# MotherboardSupply.net
KiCad netlist of a schematic drawn in Altium Designer
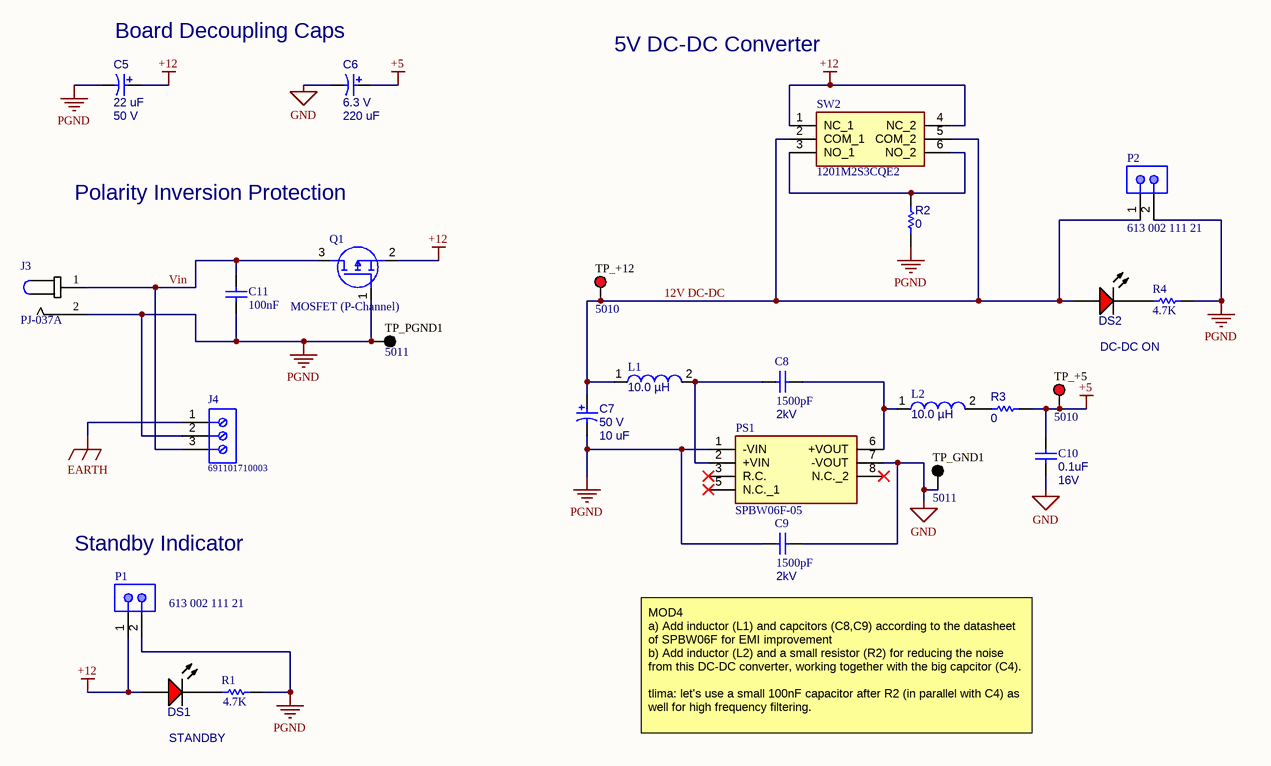
[diagram p0: MotherboardSupply.SchDoc]

(export (version "E")
  (design (tool "Eeschema 10.0.6"))
  (components
    (comp (ref "C5")
      (value "UUD1H220MCL1GS")
      (footprint "NIC-CAPA2-6.3X5.8_V")
      (fields
        (field (name "MANUFACTURER") "Nichicon")
        (field (name "RATED CAPACITANCE") "22 uF")
        (field (name "RATED VOLTAGE") "50 V")
      )
      (libsource (lib "Altium Content Vault") (part "NIC-CAP-P-2"))
    )
    (comp (ref "C6")
      (value "UUD0J221MCL1GS")
      (footprint "NIC-CAPA2-6.3X5.8_V")
      (fields
        (field (name "RATED VOLTAGE") "6.3 V")
        (field (name "RATED CAPACITANCE") "220 uF")
        (field (name "MANUFACTURER") "Nichicon")
      )
      (libsource (lib "Altium Content Vault") (part "NIC-CAP-P-2"))
    )
    (comp (ref "C7")
      (value "UUD0J221MCL1GS")
      (footprint "NIC-CAPA2-6.3X5.8_V")
      (fields
        (field (name "RATED VOLTAGE") "50 V")
        (field (name "RATED CAPACITANCE") "10 uF")
        (field (name "MANUFACTURER") "Nichicon")
      )
      (libsource (lib "Altium Content Vault") (part "NIC-CAP-P-2"))
    )
    (comp (ref "C8")
      (value "1500pF")
      (footprint "C1206")
      (description "Capacitor (Semiconductor SIM Model)")
      (fields
        (field (name "RATED VOLTAGE") "2kV")
        (field (name "Comment") "CC1206KKX7RDBB152")
        (field (name "PUBLISHER") "Altium Limited")
      )
      (libsource (lib "Miscellaneous Devices") (part "Cap Semi"))
    )
    (comp (ref "C9")
      (value "1500pF")
      (footprint "C1206")
      (description "Capacitor (Semiconductor SIM Model)")
      (fields
        (field (name "RATED VOLTAGE") "2kV")
        (field (name "Comment") "CC1206KKX7RDBB152")
        (field (name "PUBLISHER") "Altium Limited")
      )
      (libsource (lib "Miscellaneous Devices") (part "Cap Semi"))
    )
    (comp (ref "C10")
      (value "0.1uF")
      (footprint "CAPC1608X87X35LL15T15")
      (fields
        (field (name "MANUFACTURER") "Kemet")
        (field (name "PART NUMBER") "C0603C104K4RACTU")
        (field (name "RATED VOLTAGE") "16V")
      )
      (libsource (lib "Altium Content Vault") (part "CAP"))
    )
    (comp (ref "C11")
      (value "100nF")
      (footprint "CAPC1206(3216)150_M")
      (description "CAP 100nF 250V ±10% 1206 (3216 Metric) Thickness 1.45mm SMD")
      (fields (field (name "TOLERANCE") "Â±10%"))
      (libsource (lib "Altium Content Vault") (part "CAP"))
    )
    (comp (ref "DS1")
      (value "TLMS1000-GS08")
      (footprint "VISH-TLMS1000_V")
      (description "Low Current LED, 40 mW, 1.8 V, -40 to 100 degC, 2-Pin SMD (0603), RoHS, Tape and Reel")
      (fields (field (name "MANUFACTURER") "Vishay"))
      (libsource (lib "Altium Content Vault") (part "LED-RED-AK-2"))
    )
    (comp (ref "DS2")
      (value "TLMS1000-GS08")
      (footprint "VISH-TLMS1000_V")
      (description "Low Current LED, 40 mW, 1.8 V, -40 to 100 degC, 2-Pin SMD (0603), RoHS, Tape and Reel")
      (fields (field (name "MANUFACTURER") "Vishay"))
      (libsource (lib "Altium Content Vault") (part "LED-RED-AK-2"))
    )
    (comp (ref "J3")
      (value "PJ-037A")
      (footprint "*CUI_PJ-037A")
      (description "2.0 x 6.5 mm, 2.5 A, Horizontal, Through Hole, Dc Power Jack Connector")
      (fields (field (name "DIGI-KEY_PART_NUMBER") "CP-037A-ND") (field (name "MF") "CUI Inc."))
      (libsource (lib "PJ-037A") (part "PJ-037A"))
    )
    (comp (ref "J4")
      (value "691101710003")
      (footprint "691101710003")
      (description "Series 101 - 5.00 mm Horizontal Entry Modular with Pressure Clamp WR-TBL, 3 pin")
      (fields (field (name "MANUFACTURER") "Wurth Elektronik") (field (name "PUBLISHER") "WurthElektronik"))
      (libsource (lib "Altium Content Vault") (part "WE-CN-1P-F-TB3"))
    )
    (comp (ref "L1")
      (value "74477110")
      (footprint "WE-PD-L")
      (description "SMD-Shielded Power Inductor WE-PD, L = 10.0 µH")
      (fields (field (name "INDUCTANCE") "10.0 µH"))
      (libsource (lib "Altium Content Vault") (part "PAS-IND-INDUCTOR-2"))
    )
    (comp (ref "L2")
      (value "74477110")
      (footprint "WE-PD-L")
      (description "SMD-Shielded Power Inductor WE-PD, L = 10.0 µH")
      (fields (field (name "INDUCTANCE") "10.0 µH"))
      (libsource (lib "Altium Content Vault") (part "PAS-IND-INDUCTOR-2"))
    )
    (comp (ref "P1")
      (value "613 002 111 21")
      (footprint "WE-61300211121_V")
      (libsource (lib "Altium Content Vault") (part "CN-1P-M-R2"))
    )
    (comp (ref "P2")
      (value "613 002 111 21")
      (footprint "WE-61300211121_V")
      (libsource (lib "Altium Content Vault") (part "CN-1P-M-R2"))
    )
    (comp (ref "PS1")
      (value "SPBW06F-05")
      (footprint "SamacSys:SPBW06F05")
      (description "Power Supply")
      (fields (field (name "MOUSER PART NUMBER") "709-SPBW06F-05"))
      (libsource (lib "*") (part "SPBW06F-05"))
    )
    (comp (ref "Q1")
      (value "MOSFET (P-Channel)")
      (footprint "SamacSys:FFSB20120AF085")
      (description "FQB47P06TM-AM002")
      (fields (field (name "MOUSER PART NUMBER") "512-FQB47P06TM_AM002"))
      (libsource (lib "*") (part "FQB47P06TM-AM002"))
    )
    (comp (ref "R1")
      (value "4.7K")
      (footprint "RESC3216X60X45ML10T20")
      (description "CRCW12064K70JNEB")
      (fields (field (name "MANUFACTURER") "Vishay Dale"))
      (libsource (lib "Altium Content Vault") (part "RES"))
    )
    (comp (ref "R2")
      (value "0")
      (footprint "RESC3216X105X45ML10T20")
      (description "CRCW12060000Z0EA")
      (fields (field (name "MANUFACTURER") "Vishay Dale"))
      (libsource (lib "Altium Content Vault") (part "RES"))
    )
    (comp (ref "R3")
      (value "0")
      (footprint "RESC3216X105X45ML10T20")
      (description "CRCW12060000Z0EA")
      (fields (field (name "MANUFACTURER") "Vishay Dale"))
      (libsource (lib "Altium Content Vault") (part "RES"))
    )
    (comp (ref "R4")
      (value "4.7K")
      (footprint "RESC3216X60X45ML10T20")
      (description "CRCW12064K70JNEB")
      (fields (field (name "MANUFACTURER") "Vishay Dale"))
      (libsource (lib "Altium Content Vault") (part "RES"))
    )
    (comp (ref "SW2")
      (value "1201M2S3CQE2")
      (footprint "SamacSys:1201M2S3CQE2")
      (description "Switch")
      (fields (field (name "MOUSER PART NUMBER") "611-1201M2S3CQE2"))
      (libsource (lib "*") (part "1201M2S3CQE2"))
    )
    (comp (ref "TP_+5")
      (value "5010")
      (footprint "KSTN-5010_V")
      (description "Test Point, Red, Through Hole, RoHS, Bulk")
      (fields (field (name "MANUFACTURER") "Keystone"))
      (libsource (lib "Altium Content Vault") (part "TESTPOINT_RED"))
    )
    (comp (ref "TP_+12")
      (value "5010")
      (footprint "KSTN-5010_V")
      (description "Test Point, Red, Through Hole, RoHS, Bulk")
      (fields (field (name "MANUFACTURER") "Keystone"))
      (libsource (lib "Altium Content Vault") (part "TESTPOINT_RED"))
    )
    (comp (ref "TP_GND1")
      (value "5011")
      (footprint "KSTN-5011_V")
      (description "Test Point, Black, Through Hole, RoHS, Bulk")
      (fields (field (name "MANUFACTURER") "Keystone"))
      (libsource (lib "Altium Content Vault") (part "TESTPOINT_BLACK"))
    )
    (comp (ref "TP_PGND1")
      (value "5011")
      (footprint "KSTN-5011_V")
      (description "Test Point, Black, Through Hole, RoHS, Bulk")
      (fields (field (name "MANUFACTURER") "Keystone"))
      (libsource (lib "Altium Content Vault") (part "TESTPOINT_BLACK"))
    )
  )
  (nets
    (net (code "1") (name "+5") (class "Default")
      (node (ref "C10") (pin "2") (pinfunction "2_2") (pintype "passive"))
      (node (ref "C6") (pin "1") (pinfunction "1_1") (pintype "passive"))
      (node (ref "R3") (pin "2") (pinfunction "2_2") (pintype "passive"))
      (node (ref "TP_+5") (pin "1") (pinfunction "1_1") (pintype "passive"))
    )
    (net (code "2") (name "+12") (class "Default")
      (node (ref "C5") (pin "1") (pinfunction "1_1") (pintype "passive"))
      (node (ref "DS1") (pin "1") (pinfunction "A_1") (pintype "passive"))
      (node (ref "P1") (pin "1") (pinfunction "1_1") (pintype "passive"))
      (node (ref "Q1") (pin "2") (pinfunction "S_2") (pintype "passive"))
      (node (ref "SW2") (pin "1") (pinfunction "NC_1_1") (pintype "passive"))
      (node (ref "SW2") (pin "4") (pinfunction "NC_2_4") (pintype "passive"))
    )
    (net (code "3") (name "/12V DC-DC") (class "Default")
      (node (ref "C7") (pin "1") (pinfunction "1_1") (pintype "passive"))
      (node (ref "DS2") (pin "1") (pinfunction "A_1") (pintype "passive"))
      (node (ref "L1") (pin "1") (pinfunction "1_1") (pintype "passive"))
      (node (ref "P2") (pin "1") (pinfunction "1_1") (pintype "passive"))
      (node (ref "SW2") (pin "2") (pinfunction "COM_1_2") (pintype "passive"))
      (node (ref "SW2") (pin "5") (pinfunction "COM_2_5") (pintype "passive"))
      (node (ref "TP_+12") (pin "1") (pinfunction "1_1") (pintype "passive"))
    )
    (net (code "4") (name "/Vin") (class "Default")
      (node (ref "C11") (pin "1") (pinfunction "1_1") (pintype "passive"))
      (node (ref "J3") (pin "1") (pinfunction "1_1") (pintype "passive"))
      (node (ref "J4") (pin "3") (pinfunction "3_3") (pintype "passive"))
      (node (ref "Q1") (pin "3") (pinfunction "D_3") (pintype "passive"))
    )
    (net (code "5") (name "EARTH") (class "Default")
      (node (ref "J4") (pin "1") (pinfunction "1_1") (pintype "passive"))
    )
    (net (code "6") (name "GND") (class "Default")
      (node (ref "C10") (pin "1") (pinfunction "1_1") (pintype "passive"))
      (node (ref "C6") (pin "2") (pinfunction "2_2") (pintype "passive"))
      (node (ref "C9") (pin "2") (pinfunction "2_2") (pintype "passive"))
      (node (ref "PS1") (pin "7") (pinfunction "-VOUT_7") (pintype "passive"))
      (node (ref "TP_GND1") (pin "1") (pinfunction "1_1") (pintype "passive"))
    )
    (net (code "7") (name "Net-(DS1-K)") (class "Default")
      (node (ref "DS1") (pin "2") (pinfunction "K_2") (pintype "passive"))
      (node (ref "R1") (pin "1") (pinfunction "1_1") (pintype "passive"))
    )
    (net (code "8") (name "Net-(DS2-K)") (class "Default")
      (node (ref "DS2") (pin "2") (pinfunction "K_2") (pintype "passive"))
      (node (ref "R4") (pin "2") (pinfunction "2_2") (pintype "passive"))
    )
    (net (code "9") (name "Net-(L2-Pad2)") (class "Default")
      (node (ref "L2") (pin "2") (pinfunction "2_2") (pintype "passive"))
      (node (ref "R3") (pin "1") (pinfunction "1_1") (pintype "passive"))
    )
    (net (code "10") (name "Net-(PS1-+VIN)") (class "Default")
      (node (ref "C8") (pin "1") (pinfunction "1_1") (pintype "passive"))
      (node (ref "L1") (pin "2") (pinfunction "2_2") (pintype "passive"))
      (node (ref "PS1") (pin "2") (pinfunction "+VIN_2") (pintype "passive"))
    )
    (net (code "11") (name "Net-(PS1-+VOUT)") (class "Default")
      (node (ref "C8") (pin "2") (pinfunction "2_2") (pintype "passive"))
      (node (ref "L2") (pin "1") (pinfunction "1_1") (pintype "passive"))
      (node (ref "PS1") (pin "6") (pinfunction "+VOUT_6") (pintype "passive"))
    )
    (net (code "12") (name "Net-(SW2-NO_1)") (class "Default")
      (node (ref "R2") (pin "1") (pinfunction "1_1") (pintype "passive"))
      (node (ref "SW2") (pin "3") (pinfunction "NO_1_3") (pintype "passive"))
      (node (ref "SW2") (pin "6") (pinfunction "NO_2_6") (pintype "passive"))
    )
    (net (code "13") (name "PGND") (class "Default")
      (node (ref "C11") (pin "2") (pinfunction "2_2") (pintype "passive"))
      (node (ref "C5") (pin "2") (pinfunction "2_2") (pintype "passive"))
      (node (ref "C7") (pin "2") (pinfunction "2_2") (pintype "passive"))
      (node (ref "C9") (pin "1") (pinfunction "1_1") (pintype "passive"))
      (node (ref "J3") (pin "2") (pinfunction "2_2") (pintype "passive"))
      (node (ref "J4") (pin "2") (pinfunction "2_2") (pintype "passive"))
      (node (ref "P1") (pin "2") (pinfunction "2_2") (pintype "passive"))
      (node (ref "P2") (pin "2") (pinfunction "2_2") (pintype "passive"))
      (node (ref "PS1") (pin "1") (pinfunction "-VIN_1") (pintype "passive"))
      (node (ref "Q1") (pin "1") (pinfunction "G_1") (pintype "passive"))
      (node (ref "R1") (pin "2") (pinfunction "2_2") (pintype "passive"))
      (node (ref "R2") (pin "2") (pinfunction "2_2") (pintype "passive"))
      (node (ref "R4") (pin "1") (pinfunction "1_1") (pintype "passive"))
      (node (ref "TP_PGND1") (pin "1") (pinfunction "1_1") (pintype "passive"))
    )
    (net (code "14") (name "unconnected-(PS1-N.C._1-Pad5)") (class "Default")
      (node (ref "PS1") (pin "5") (pinfunction "N.C._1_5") (pintype "passive+no_connect"))
    )
    (net (code "15") (name "unconnected-(PS1-N.C._2-Pad8)") (class "Default")
      (node (ref "PS1") (pin "8") (pinfunction "N.C._2_8") (pintype "passive+no_connect"))
    )
    (net (code "16") (name "unconnected-(PS1-R.C.-Pad3)") (class "Default")
      (node (ref "PS1") (pin "3") (pinfunction "R.C._3") (pintype "passive+no_connect"))
    )
  )
)
